# fullprop.net
KiCad netlist of a schematic drawn in EAGLE
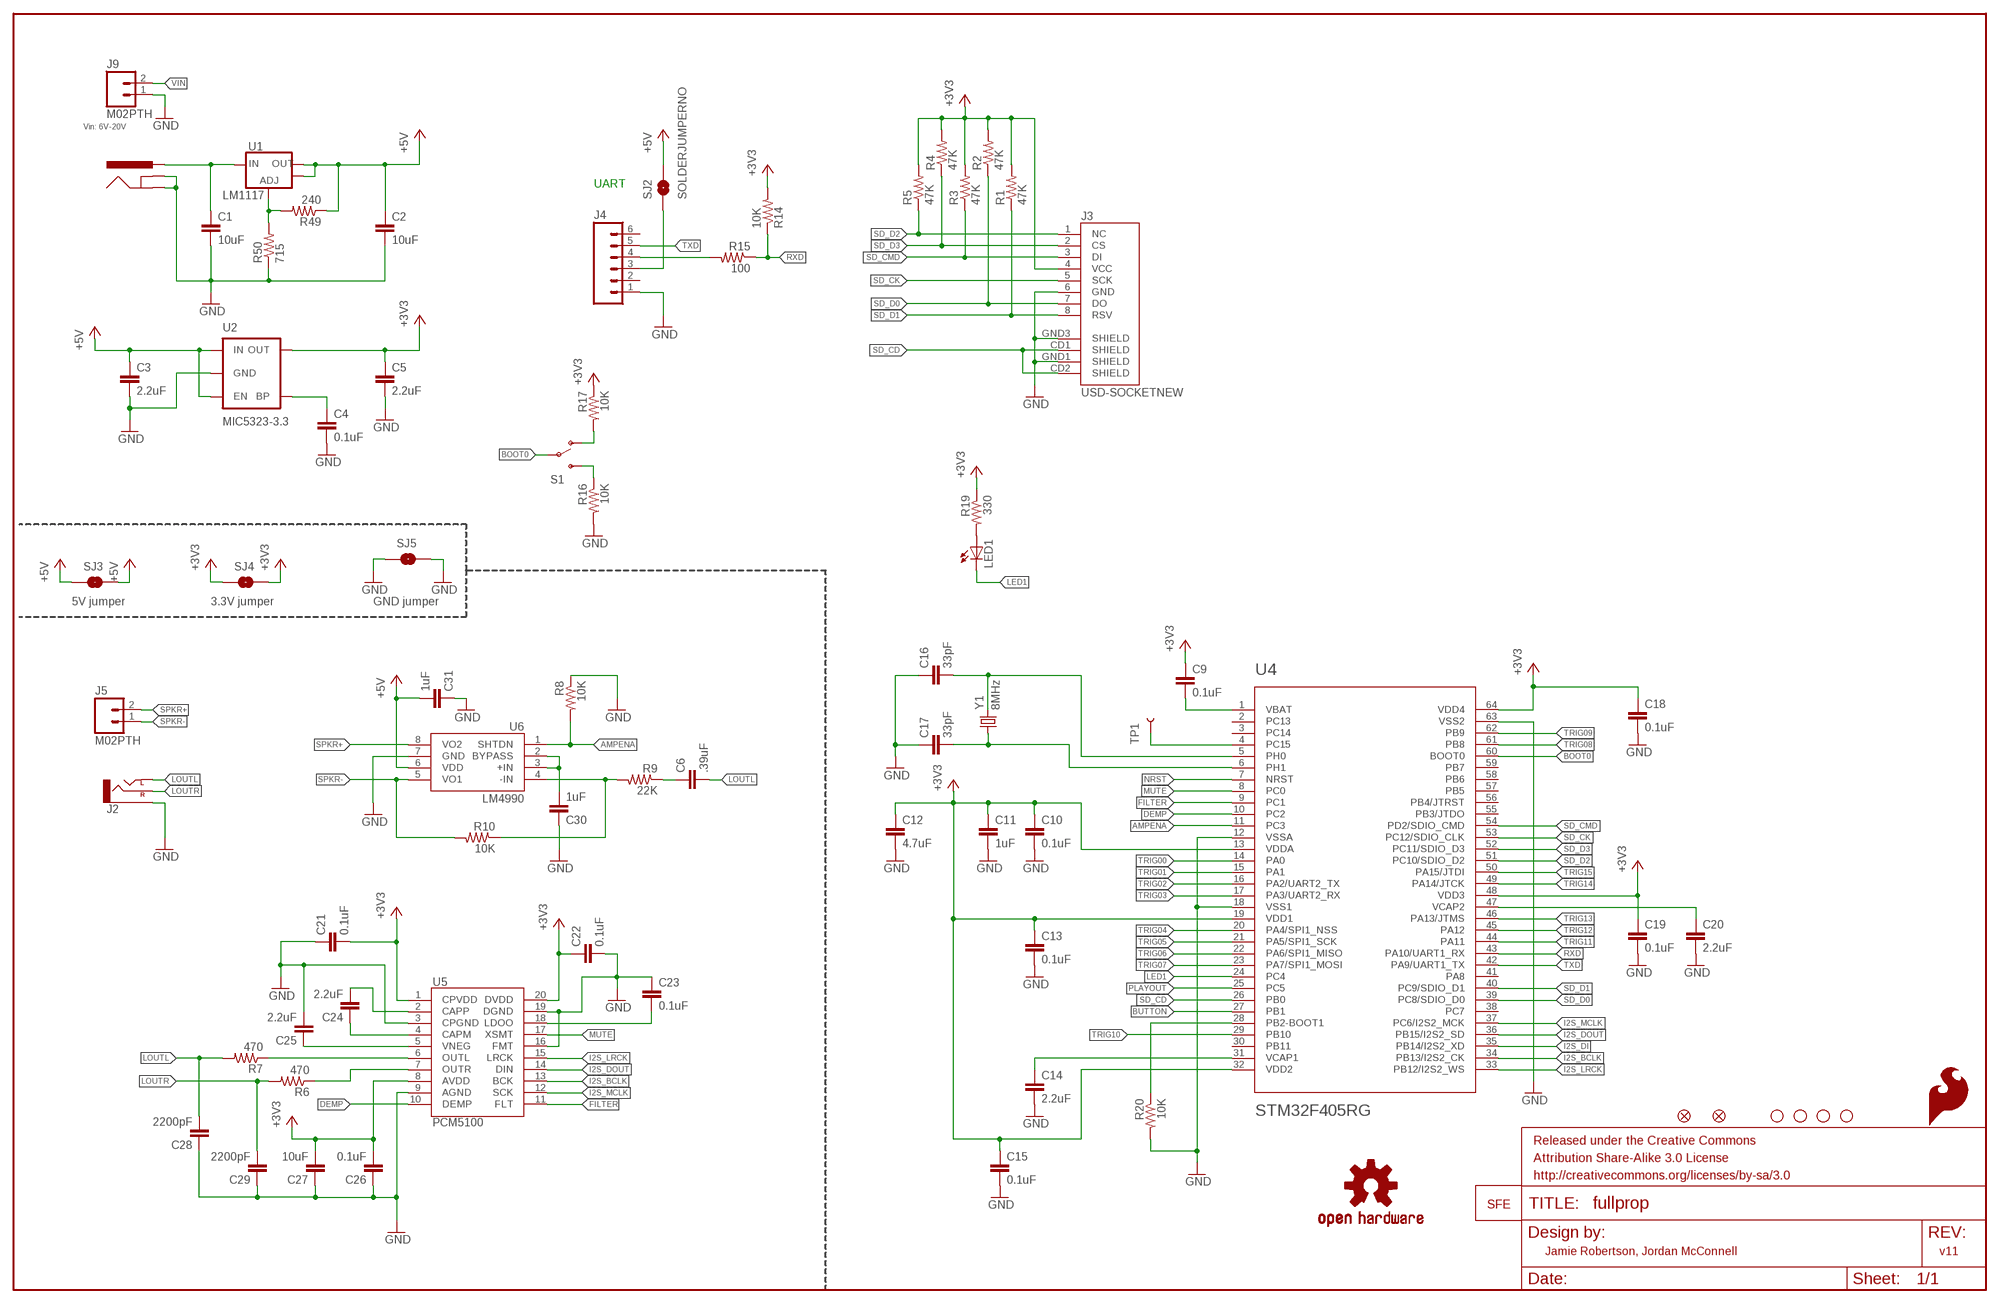
[diagram p0: schematic, sheet 1]

(export (version "E")
  (design (tool "Eeschema 10.0.6"))
  (components
    (comp (ref "C1")
      (value "10uF")
      (footprint "eagle-import:1210")
      (libsource (lib "eagle-import") (part "10UF50V20%(1210)"))
    )
    (comp (ref "C2")
      (value "10uF")
      (footprint "eagle-import:0805")
      (libsource (lib "eagle-import") (part "1UF-25V-10%(0805)"))
    )
    (comp (ref "C3")
      (value "2.2uF")
      (footprint "eagle-import:0805")
      (libsource (lib "eagle-import") (part "1UF-25V-10%(0805)"))
    )
    (comp (ref "C4")
      (value "0.1uF")
      (footprint "eagle-import:0603-CAP")
      (libsource (lib "eagle-import") (part "CAP0603-CAP"))
    )
    (comp (ref "C5")
      (value "2.2uF")
      (footprint "eagle-import:0805")
      (libsource (lib "eagle-import") (part "1UF-25V-10%(0805)"))
    )
    (comp (ref "C6")
      (value ".39uF")
      (footprint "eagle-import:0603-CAP")
      (libsource (lib "eagle-import") (part "CAP0603-CAP"))
    )
    (comp (ref "C9")
      (value "0.1uF")
      (footprint "eagle-import:0603-CAP")
      (libsource (lib "eagle-import") (part "CAP0603-CAP"))
    )
    (comp (ref "C10")
      (value "0.1uF")
      (footprint "eagle-import:0603-CAP")
      (libsource (lib "eagle-import") (part "CAP0603-CAP"))
    )
    (comp (ref "C11")
      (value "1uF")
      (footprint "eagle-import:0603-CAP")
      (libsource (lib "eagle-import") (part "CAP0603-CAP"))
    )
    (comp (ref "C12")
      (value "4.7uF")
      (footprint "eagle-import:0603-CAP")
      (libsource (lib "eagle-import") (part "CAP0603-CAP"))
    )
    (comp (ref "C13")
      (value "0.1uF")
      (footprint "eagle-import:0603-CAP")
      (libsource (lib "eagle-import") (part "CAP0603-CAP"))
    )
    (comp (ref "C14")
      (value "2.2uF")
      (footprint "eagle-import:0603-CAP")
      (libsource (lib "eagle-import") (part "CAP0603-CAP"))
    )
    (comp (ref "C15")
      (value "0.1uF")
      (footprint "eagle-import:0603-CAP")
      (libsource (lib "eagle-import") (part "CAP0603-CAP"))
    )
    (comp (ref "C16")
      (value "33pF")
      (footprint "eagle-import:0603-CAP")
      (libsource (lib "eagle-import") (part "CAP0603-CAP"))
    )
    (comp (ref "C17")
      (value "33pF")
      (footprint "eagle-import:0603-CAP")
      (libsource (lib "eagle-import") (part "CAP0603-CAP"))
    )
    (comp (ref "C18")
      (value "0.1uF")
      (footprint "eagle-import:0603-CAP")
      (libsource (lib "eagle-import") (part "CAP0603-CAP"))
    )
    (comp (ref "C19")
      (value "0.1uF")
      (footprint "eagle-import:0603-CAP")
      (libsource (lib "eagle-import") (part "CAP0603-CAP"))
    )
    (comp (ref "C20")
      (value "2.2uF")
      (footprint "eagle-import:0603-CAP")
      (libsource (lib "eagle-import") (part "CAP0603-CAP"))
    )
    (comp (ref "C21")
      (value "0.1uF")
      (footprint "eagle-import:0603-CAP")
      (libsource (lib "eagle-import") (part "CAP0603-CAP"))
    )
    (comp (ref "C22")
      (value "0.1uF")
      (footprint "eagle-import:0603-CAP")
      (libsource (lib "eagle-import") (part "CAP0603-CAP"))
    )
    (comp (ref "C23")
      (value "0.1uF")
      (footprint "eagle-import:0603-CAP")
      (libsource (lib "eagle-import") (part "CAP0603-CAP"))
    )
    (comp (ref "C24")
      (value "2.2uF")
      (footprint "eagle-import:0603-CAP")
      (libsource (lib "eagle-import") (part "CAP0603-CAP"))
    )
    (comp (ref "C25")
      (value "2.2uF")
      (footprint "eagle-import:0603-CAP")
      (libsource (lib "eagle-import") (part "CAP0603-CAP"))
    )
    (comp (ref "C26")
      (value "0.1uF")
      (footprint "eagle-import:0603-CAP")
      (libsource (lib "eagle-import") (part "CAP0603-CAP"))
    )
    (comp (ref "C27")
      (value "10uF")
      (footprint "eagle-import:0603-CAP")
      (libsource (lib "eagle-import") (part "CAP0603-CAP"))
    )
    (comp (ref "C28")
      (value "2200pF")
      (footprint "eagle-import:0603-CAP")
      (libsource (lib "eagle-import") (part "CAP0603-CAP"))
    )
    (comp (ref "C29")
      (value "2200pF")
      (footprint "eagle-import:0603-CAP")
      (libsource (lib "eagle-import") (part "CAP0603-CAP"))
    )
    (comp (ref "C30")
      (value "1uF")
      (footprint "eagle-import:0603-CAP")
      (libsource (lib "eagle-import") (part "CAP0603-CAP"))
    )
    (comp (ref "C31")
      (value "1uF")
      (footprint "eagle-import:0603-CAP")
      (libsource (lib "eagle-import") (part "CAP0603-CAP"))
    )
    (comp (ref "FID1")
      (value "FIDUCIAL1X2")
      (footprint "eagle-import:FIDUCIAL-1X2")
      (libsource (lib "eagle-import") (part "FIDUCIAL1X2"))
    )
    (comp (ref "FID2")
      (value "FIDUCIAL1X2")
      (footprint "eagle-import:FIDUCIAL-1X2")
      (libsource (lib "eagle-import") (part "FIDUCIAL1X2"))
    )
    (comp (ref "FRAME2")
      (value "FRAME-LEDGER")
      (footprint "eagle-import:CREATIVE_COMMONS")
      (libsource (lib "eagle-import") (part "FRAME-LEDGER"))
    )
    (comp (ref "J1")
      (value "5.5x2.1mm Barrel")
      (footprint "eagle-import:POWER_JACK_SMD_OVERPASTE_REDBOARD_0603")
      (libsource (lib "eagle-import") (part "POWER_JACKOVERPASTE_REDBOARD_0603"))
    )
    (comp (ref "J2")
      (value "AUDIO-JACKSMD2")
      (footprint "eagle-import:AUDIO-JACK-3.5MM-SMD")
      (libsource (lib "eagle-import") (part "AUDIO-JACKSMD2"))
    )
    (comp (ref "J3")
      (value "USD-SOCKETNEW")
      (footprint "eagle-import:MICRO-SD-SOCKET-PP")
      (libsource (lib "eagle-import") (part "USD-SOCKETNEW"))
    )
    (comp (ref "J4")
      (value "M06SIP")
      (footprint "eagle-import:1X06")
      (libsource (lib "eagle-import") (part "M06SIP"))
    )
    (comp (ref "J5")
      (value "M02PTH")
      (footprint "eagle-import:1X02")
      (libsource (lib "eagle-import") (part "M02PTH"))
    )
    (comp (ref "J9")
      (value "M02PTH")
      (footprint "eagle-import:1X02")
      (libsource (lib "eagle-import") (part "M02PTH"))
    )
    (comp (ref "LED1")
      (value "LED0603")
      (footprint "eagle-import:LED-0603")
      (libsource (lib "eagle-import") (part "LED0603"))
    )
    (comp (ref "LOGO1")
      (value "OSHW-LOGOL")
      (footprint "eagle-import:OSHW-LOGO-L")
      (libsource (lib "eagle-import") (part "OSHW-LOGOL"))
    )
    (comp (ref "LOGO2")
      (value "LOGO-SFENEW")
      (footprint "eagle-import:SFE-NEW-WEBLOGO")
      (libsource (lib "eagle-import") (part "LOGO-SFENEW"))
    )
    (comp (ref "LOGO4")
      (value "SFE_LOGO_FLAME.2_INCH")
      (footprint "eagle-import:SFE_LOGO_FLAME_.2")
      (libsource (lib "eagle-import") (part "SFE_LOGO_FLAME.2_INCH"))
    )
    (comp (ref "R1")
      (value "47K")
      (footprint "eagle-import:0603-RES")
      (libsource (lib "eagle-import") (part "RESISTOR0603-RES"))
    )
    (comp (ref "R2")
      (value "47K")
      (footprint "eagle-import:0603-RES")
      (libsource (lib "eagle-import") (part "RESISTOR0603-RES"))
    )
    (comp (ref "R3")
      (value "47K")
      (footprint "eagle-import:0603-RES")
      (libsource (lib "eagle-import") (part "RESISTOR0603-RES"))
    )
    (comp (ref "R4")
      (value "47K")
      (footprint "eagle-import:0603-RES")
      (libsource (lib "eagle-import") (part "RESISTOR0603-RES"))
    )
    (comp (ref "R5")
      (value "47K")
      (footprint "eagle-import:0603-RES")
      (libsource (lib "eagle-import") (part "RESISTOR0603-RES"))
    )
    (comp (ref "R6")
      (value "470")
      (footprint "eagle-import:0603-RES")
      (libsource (lib "eagle-import") (part "RESISTOR0603-RES"))
    )
    (comp (ref "R7")
      (value "470")
      (footprint "eagle-import:0603-RES")
      (libsource (lib "eagle-import") (part "RESISTOR0603-RES"))
    )
    (comp (ref "R8")
      (value "10K")
      (footprint "eagle-import:0603-RES")
      (libsource (lib "eagle-import") (part "RESISTOR0603-RES"))
    )
    (comp (ref "R9")
      (value "22K")
      (footprint "eagle-import:0603-RES")
      (libsource (lib "eagle-import") (part "RESISTOR0603-RES"))
    )
    (comp (ref "R10")
      (value "10K")
      (footprint "eagle-import:0603-RES")
      (libsource (lib "eagle-import") (part "RESISTOR0603-RES"))
    )
    (comp (ref "R14")
      (value "10K")
      (footprint "eagle-import:0603-RES")
      (libsource (lib "eagle-import") (part "RESISTOR0603-RES"))
    )
    (comp (ref "R15")
      (value "100")
      (footprint "eagle-import:0603-RES")
      (libsource (lib "eagle-import") (part "RESISTOR0603-RES"))
    )
    (comp (ref "R16")
      (value "10K")
      (footprint "eagle-import:0603-RES")
      (libsource (lib "eagle-import") (part "RESISTOR0603-RES"))
    )
    (comp (ref "R17")
      (value "10K")
      (footprint "eagle-import:0603-RES")
      (libsource (lib "eagle-import") (part "RESISTOR0603-RES"))
    )
    (comp (ref "R19")
      (value "330")
      (footprint "eagle-import:0603-RES")
      (libsource (lib "eagle-import") (part "RESISTOR0603-RES"))
    )
    (comp (ref "R20")
      (value "10K")
      (footprint "eagle-import:0603-RES")
      (libsource (lib "eagle-import") (part "RESISTOR0603-RES"))
    )
    (comp (ref "R49")
      (value "240")
      (footprint "eagle-import:0603-RES")
      (libsource (lib "eagle-import") (part "240OHM1/10W1%(0603)"))
    )
    (comp (ref "R50")
      (value "715")
      (footprint "eagle-import:0603-RES")
      (libsource (lib "eagle-import") (part "RESISTOR0603"))
    )
    (comp (ref "S1")
      (value "SWITCH-SPDT-SMD-A")
      (footprint "eagle-import:SWITCH-SPST-SMD-A")
      (libsource (lib "eagle-import") (part "SWITCH-SPDT-SMD-A"))
    )
    (comp (ref "SJ2")
      (value "SOLDERJUMPERNO")
      (footprint "eagle-import:SJ_2S-NO")
      (libsource (lib "eagle-import") (part "SOLDERJUMPERNO"))
    )
    (comp (ref "SJ3")
      (value "SOLDERJUMPERTRACE")
      (footprint "eagle-import:SJ_2S-TRACE")
      (libsource (lib "eagle-import") (part "SOLDERJUMPERTRACE"))
    )
    (comp (ref "SJ4")
      (value "SOLDERJUMPERTRACE")
      (footprint "eagle-import:SJ_2S-TRACE")
      (libsource (lib "eagle-import") (part "SOLDERJUMPERTRACE"))
    )
    (comp (ref "SJ5")
      (value "SOLDERJUMPERTRACE")
      (footprint "eagle-import:SJ_2S-TRACE")
      (libsource (lib "eagle-import") (part "SOLDERJUMPERTRACE"))
    )
    (comp (ref "STANDOFF1")
      (value "STAND-OFF")
      (footprint "eagle-import:STAND-OFF")
      (libsource (lib "eagle-import") (part "STAND-OFF"))
    )
    (comp (ref "STANDOFF2")
      (value "STAND-OFF")
      (footprint "eagle-import:STAND-OFF")
      (libsource (lib "eagle-import") (part "STAND-OFF"))
    )
    (comp (ref "STANDOFF3")
      (value "STAND-OFF")
      (footprint "eagle-import:STAND-OFF")
      (libsource (lib "eagle-import") (part "STAND-OFF"))
    )
    (comp (ref "STANDOFF4")
      (value "STAND-OFF")
      (footprint "eagle-import:STAND-OFF")
      (libsource (lib "eagle-import") (part "STAND-OFF"))
    )
    (comp (ref "TP1")
      (value "TEST-POINTTP_15TH_THRU")
      (footprint "eagle-import:TP_15TH")
      (libsource (lib "eagle-import") (part "TEST-POINTTP_15TH_THRU"))
    )
    (comp (ref "U1")
      (value "V_REG_LM1117SOT223")
      (footprint "eagle-import:SOT223")
      (libsource (lib "eagle-import") (part "V_REG_LM1117SOT223"))
    )
    (comp (ref "U2")
      (value "MIC5323-3.3")
      (footprint "eagle-import:SOT23-5")
      (libsource (lib "eagle-import") (part "MIC52053.3V"))
    )
    (comp (ref "U4")
      (value "STM32F405RG")
      (footprint "eagle-import:TQFP64")
      (libsource (lib "eagle-import") (part "STM32F405RG"))
    )
    (comp (ref "U5")
      (value "PCM5100")
      (footprint "eagle-import:PW_R-PDSO-G20")
      (libsource (lib "eagle-import") (part "PCM5100"))
    )
    (comp (ref "U6")
      (value "LM4990")
      (footprint "eagle-import:S-PDSO-G08")
      (libsource (lib "eagle-import") (part "LM4990"))
    )
    (comp (ref "Y1")
      (value "8MHz")
      (footprint "eagle-import:HC49UP")
      (libsource (lib "eagle-import") (part "CRYSTALSMD"))
    )
  )
  (nets
    (net (code "1") (name "+3V3") (class "Default")
      (node (ref "C10") (pin "1") (pinfunction "1_1") (pintype "passive"))
      (node (ref "C11") (pin "1") (pinfunction "1_1") (pintype "passive"))
      (node (ref "C12") (pin "1") (pinfunction "1_1") (pintype "passive"))
      (node (ref "C13") (pin "1") (pinfunction "1_1") (pintype "passive"))
      (node (ref "C15") (pin "1") (pinfunction "1_1") (pintype "passive"))
      (node (ref "C18") (pin "1") (pinfunction "1_1") (pintype "passive"))
      (node (ref "C19") (pin "1") (pinfunction "1_1") (pintype "passive"))
      (node (ref "C21") (pin "2") (pinfunction "2_2") (pintype "passive"))
      (node (ref "C22") (pin "1") (pinfunction "1_1") (pintype "passive"))
      (node (ref "C26") (pin "2") (pinfunction "2_2") (pintype "passive"))
      (node (ref "C27") (pin "2") (pinfunction "2_2") (pintype "passive"))
      (node (ref "C5") (pin "1") (pinfunction "1_1") (pintype "passive"))
      (node (ref "C9") (pin "1") (pinfunction "1_1") (pintype "passive"))
      (node (ref "J3") (pin "4") (pinfunction "VCC_4") (pintype "bidirectional"))
      (node (ref "R1") (pin "2") (pinfunction "2_2") (pintype "passive"))
      (node (ref "R14") (pin "2") (pinfunction "2_2") (pintype "passive"))
      (node (ref "R17") (pin "1") (pinfunction "1_1") (pintype "passive"))
      (node (ref "R19") (pin "1") (pinfunction "1_1") (pintype "passive"))
      (node (ref "R2") (pin "2") (pinfunction "2_2") (pintype "passive"))
      (node (ref "R3") (pin "2") (pinfunction "2_2") (pintype "passive"))
      (node (ref "R4") (pin "2") (pinfunction "2_2") (pintype "passive"))
      (node (ref "R5") (pin "2") (pinfunction "2_2") (pintype "passive"))
      (node (ref "SJ4") (pin "1") (pinfunction "1_1") (pintype "passive"))
      (node (ref "SJ4") (pin "2") (pinfunction "2_2") (pintype "passive"))
      (node (ref "U2") (pin "5") (pinfunction "OUT_5") (pintype "passive"))
      (node (ref "U4") (pin "13") (pinfunction "VDDA_13") (pintype "bidirectional"))
      (node (ref "U4") (pin "19") (pinfunction "VDD1_19") (pintype "bidirectional"))
      (node (ref "U4") (pin "32") (pinfunction "VDD2_32") (pintype "bidirectional"))
      (node (ref "U4") (pin "48") (pinfunction "VDD3_48") (pintype "bidirectional"))
      (node (ref "U4") (pin "64") (pinfunction "VDD4_64") (pintype "bidirectional"))
      (node (ref "U5") (pin "1") (pinfunction "CPVDD_1") (pintype "bidirectional"))
      (node (ref "U5") (pin "20") (pinfunction "DVDD_20") (pintype "bidirectional"))
      (node (ref "U5") (pin "8") (pinfunction "AVDD_8") (pintype "bidirectional"))
    )
    (net (code "2") (name "+5V") (class "Default")
      (node (ref "C2") (pin "1") (pinfunction "1_1") (pintype "passive"))
      (node (ref "C3") (pin "1") (pinfunction "1_1") (pintype "passive"))
      (node (ref "C31") (pin "2") (pinfunction "2_2") (pintype "passive"))
      (node (ref "R49") (pin "1") (pinfunction "1_1") (pintype "passive"))
      (node (ref "SJ2") (pin "2") (pinfunction "2_2") (pintype "passive"))
      (node (ref "SJ3") (pin "1") (pinfunction "1_1") (pintype "passive"))
      (node (ref "SJ3") (pin "2") (pinfunction "2_2") (pintype "passive"))
      (node (ref "U1") (pin "2") (pinfunction "OUT_2") (pintype "output"))
      (node (ref "U1") (pin "4") (pinfunction "OUT_4") (pintype "output"))
      (node (ref "U2") (pin "1") (pinfunction "IN_1") (pintype "input"))
      (node (ref "U2") (pin "3") (pinfunction "EN_3") (pintype "input"))
      (node (ref "U6") (pin "6") (pinfunction "VDD_6") (pintype "bidirectional"))
    )
    (net (code "3") (name "AMPENA") (class "Default")
      (node (ref "R8") (pin "2") (pinfunction "2_2") (pintype "passive"))
      (node (ref "U4") (pin "11") (pinfunction "PC3_11") (pintype "bidirectional"))
      (node (ref "U6") (pin "1") (pinfunction "SHTDN_1") (pintype "bidirectional"))
    )
    (net (code "4") (name "BOOT0") (class "Default")
      (node (ref "S1") (pin "2") (pinfunction "P_2") (pintype "passive"))
      (node (ref "U4") (pin "60") (pinfunction "BOOT0_60") (pintype "bidirectional"))
    )
    (net (code "5") (name "BUTTON") (class "Default")
      (node (ref "U4") (pin "27") (pinfunction "PB1_27") (pintype "bidirectional"))
    )
    (net (code "6") (name "DEMP") (class "Default")
      (node (ref "U4") (pin "10") (pinfunction "PC2_10") (pintype "bidirectional"))
      (node (ref "U5") (pin "10") (pinfunction "DEMP_10") (pintype "bidirectional"))
    )
    (net (code "7") (name "FILTER") (class "Default")
      (node (ref "U4") (pin "9") (pinfunction "PC1_9") (pintype "bidirectional"))
      (node (ref "U5") (pin "11") (pinfunction "FLT_11") (pintype "bidirectional"))
    )
    (net (code "8") (name "GND") (class "Default")
      (node (ref "C1") (pin "2") (pinfunction "2_2") (pintype "passive"))
      (node (ref "C10") (pin "2") (pinfunction "2_2") (pintype "passive"))
      (node (ref "C11") (pin "2") (pinfunction "2_2") (pintype "passive"))
      (node (ref "C12") (pin "2") (pinfunction "2_2") (pintype "passive"))
      (node (ref "C13") (pin "2") (pinfunction "2_2") (pintype "passive"))
      (node (ref "C14") (pin "2") (pinfunction "2_2") (pintype "passive"))
      (node (ref "C15") (pin "2") (pinfunction "2_2") (pintype "passive"))
      (node (ref "C16") (pin "1") (pinfunction "1_1") (pintype "passive"))
      (node (ref "C17") (pin "1") (pinfunction "1_1") (pintype "passive"))
      (node (ref "C18") (pin "2") (pinfunction "2_2") (pintype "passive"))
      (node (ref "C19") (pin "2") (pinfunction "2_2") (pintype "passive"))
      (node (ref "C2") (pin "2") (pinfunction "2_2") (pintype "passive"))
      (node (ref "C20") (pin "2") (pinfunction "2_2") (pintype "passive"))
      (node (ref "C21") (pin "1") (pinfunction "1_1") (pintype "passive"))
      (node (ref "C22") (pin "2") (pinfunction "2_2") (pintype "passive"))
      (node (ref "C23") (pin "1") (pinfunction "1_1") (pintype "passive"))
      (node (ref "C25") (pin "2") (pinfunction "2_2") (pintype "passive"))
      (node (ref "C26") (pin "1") (pinfunction "1_1") (pintype "passive"))
      (node (ref "C27") (pin "1") (pinfunction "1_1") (pintype "passive"))
      (node (ref "C28") (pin "1") (pinfunction "1_1") (pintype "passive"))
      (node (ref "C29") (pin "1") (pinfunction "1_1") (pintype "passive"))
      (node (ref "C3") (pin "2") (pinfunction "2_2") (pintype "passive"))
      (node (ref "C30") (pin "1") (pinfunction "1_1") (pintype "passive"))
      (node (ref "C31") (pin "1") (pinfunction "1_1") (pintype "passive"))
      (node (ref "C4") (pin "2") (pinfunction "2_2") (pintype "passive"))
      (node (ref "C5") (pin "2") (pinfunction "2_2") (pintype "passive"))
      (node (ref "J1") (pin "GND") (pinfunction "GNDBREAK_GND") (pintype "bidirectional"))
      (node (ref "J1") (pin "P$4") (pinfunction "GND_P$4") (pintype "bidirectional"))
      (node (ref "J2") (pin "SLEEVE") (pinfunction "SLEEVE_SLEEVE") (pintype "bidirectional"))
      (node (ref "J3") (pin "6") (pinfunction "GND_6") (pintype "bidirectional"))
      (node (ref "J3") (pin "GND1") (pinfunction "SHIELD_GND1") (pintype "bidirectional"))
      (node (ref "J3") (pin "GND3") (pinfunction "SHIELD_GND3") (pintype "bidirectional"))
      (node (ref "J4") (pin "1") (pinfunction "1_1") (pintype "passive"))
      (node (ref "J9") (pin "1") (pinfunction "1_1") (pintype "passive"))
      (node (ref "R16") (pin "2") (pinfunction "2_2") (pintype "passive"))
      (node (ref "R20") (pin "2") (pinfunction "2_2") (pintype "passive"))
      (node (ref "R50") (pin "1") (pinfunction "1_1") (pintype "passive"))
      (node (ref "R8") (pin "1") (pinfunction "1_1") (pintype "passive"))
      (node (ref "SJ5") (pin "1") (pinfunction "1_1") (pintype "passive"))
      (node (ref "SJ5") (pin "2") (pinfunction "2_2") (pintype "passive"))
      (node (ref "U2") (pin "2") (pinfunction "GND_2") (pintype "input"))
      (node (ref "U4") (pin "12") (pinfunction "VSSA_12") (pintype "bidirectional"))
      (node (ref "U4") (pin "18") (pinfunction "VSS1_18") (pintype "bidirectional"))
      (node (ref "U4") (pin "63") (pinfunction "VSS2_63") (pintype "bidirectional"))
      (node (ref "U5") (pin "16") (pinfunction "FMT_16") (pintype "bidirectional"))
      (node (ref "U5") (pin "19") (pinfunction "DGND_19") (pintype "bidirectional"))
      (node (ref "U5") (pin "3") (pinfunction "CPGND_3") (pintype "bidirectional"))
      (node (ref "U5") (pin "9") (pinfunction "AGND_9") (pintype "bidirectional"))
      (node (ref "U6") (pin "7") (pinfunction "GND_7") (pintype "bidirectional"))
    )
    (net (code "9") (name "I2S_BCLK") (class "Default")
      (node (ref "U4") (pin "34") (pinfunction "PB13/I2S2_CK_34") (pintype "bidirectional"))
      (node (ref "U5") (pin "13") (pinfunction "BCK_13") (pintype "bidirectional"))
    )
    (net (code "10") (name "I2S_DI") (class "Default")
      (node (ref "U4") (pin "35") (pinfunction "PB14/I2S2_XD_35") (pintype "bidirectional"))
    )
    (net (code "11") (name "I2S_DOUT") (class "Default")
      (node (ref "U4") (pin "36") (pinfunction "PB15/I2S2_SD_36") (pintype "bidirectional"))
      (node (ref "U5") (pin "14") (pinfunction "DIN_14") (pintype "bidirectional"))
    )
    (net (code "12") (name "I2S_LRCK") (class "Default")
      (node (ref "U4") (pin "33") (pinfunction "PB12/I2S2_WS_33") (pintype "bidirectional"))
      (node (ref "U5") (pin "15") (pinfunction "LRCK_15") (pintype "bidirectional"))
    )
    (net (code "13") (name "I2S_MCLK") (class "Default")
      (node (ref "U4") (pin "37") (pinfunction "PC6/I2S2_MCK_37") (pintype "bidirectional"))
      (node (ref "U5") (pin "12") (pinfunction "SCK_12") (pintype "bidirectional"))
    )
    (net (code "14") (name "LED1") (class "Default")
      (node (ref "LED1") (pin "C") (pinfunction "C_C") (pintype "passive"))
      (node (ref "U4") (pin "24") (pinfunction "PC4_24") (pintype "bidirectional"))
    )
    (net (code "15") (name "LOUTL") (class "Default")
      (node (ref "C28") (pin "2") (pinfunction "2_2") (pintype "passive"))
      (node (ref "C6") (pin "2") (pinfunction "2_2") (pintype "passive"))
      (node (ref "J2") (pin "TIP") (pinfunction "LEFT_TIP") (pintype "bidirectional"))
      (node (ref "R7") (pin "2") (pinfunction "2_2") (pintype "passive"))
    )
    (net (code "16") (name "LOUTR") (class "Default")
      (node (ref "C29") (pin "2") (pinfunction "2_2") (pintype "passive"))
      (node (ref "J2") (pin "RING") (pinfunction "RIGHT_RING") (pintype "bidirectional"))
      (node (ref "R6") (pin "2") (pinfunction "2_2") (pintype "passive"))
    )
    (net (code "17") (name "MUTE") (class "Default")
      (node (ref "U4") (pin "8") (pinfunction "PC0_8") (pintype "bidirectional"))
      (node (ref "U5") (pin "17") (pinfunction "XSMT_17") (pintype "bidirectional"))
    )
    (net (code "18") (name "NRST") (class "Default")
      (node (ref "U4") (pin "7") (pinfunction "NRST_7") (pintype "bidirectional"))
    )
    (net (code "19") (name "Net-(C6-Pad1)") (class "Default")
      (node (ref "C6") (pin "1") (pinfunction "1_1") (pintype "passive"))
      (node (ref "R9") (pin "1") (pinfunction "1_1") (pintype "passive"))
    )
    (net (code "20") (name "Net-(J4-Pad3)") (class "Default")
      (node (ref "J4") (pin "3") (pinfunction "3_3") (pintype "passive"))
      (node (ref "SJ2") (pin "1") (pinfunction "1_1") (pintype "passive"))
    )
    (net (code "21") (name "Net-(J4-Pad4)") (class "Default")
      (node (ref "J4") (pin "4") (pinfunction "4_4") (pintype "passive"))
      (node (ref "R15") (pin "2") (pinfunction "2_2") (pintype "passive"))
    )
    (net (code "22") (name "Net-(LED1-PadA)") (class "Default")
      (node (ref "LED1") (pin "A") (pinfunction "A_A") (pintype "passive"))
      (node (ref "R19") (pin "2") (pinfunction "2_2") (pintype "passive"))
    )
    (net (code "23") (name "Net-(S1-O)") (class "Default")
      (node (ref "R17") (pin "2") (pinfunction "2_2") (pintype "passive"))
      (node (ref "S1") (pin "1") (pinfunction "O_1") (pintype "passive"))
    )
    (net (code "24") (name "Net-(S1-S)") (class "Default")
      (node (ref "R16") (pin "1") (pinfunction "1_1") (pintype "passive"))
      (node (ref "S1") (pin "3") (pinfunction "S_3") (pintype "passive"))
    )
    (net (code "25") (name "Net-(TP1-1)") (class "Default")
      (node (ref "TP1") (pin "P$1") (pinfunction "1_P$1") (pintype "bidirectional"))
      (node (ref "U4") (pin "4") (pinfunction "PC15_4") (pintype "bidirectional"))
    )
    (net (code "26") (name "Net-(U1-ADJ)") (class "Default")
      (node (ref "R49") (pin "2") (pinfunction "2_2") (pintype "passive"))
      (node (ref "R50") (pin "2") (pinfunction "2_2") (pintype "passive"))
      (node (ref "U1") (pin "1") (pinfunction "ADJ_1") (pintype "input"))
    )
    (net (code "27") (name "Net-(U2-BP)") (class "Default")
      (node (ref "C4") (pin "1") (pinfunction "1_1") (pintype "passive"))
      (node (ref "U2") (pin "4") (pinfunction "BP_4") (pintype "input"))
    )
    (net (code "28") (name "Net-(U4-PB2-BOOT1)") (class "Default")
      (node (ref "R20") (pin "1") (pinfunction "1_1") (pintype "passive"))
      (node (ref "U4") (pin "28") (pinfunction "PB2-BOOT1_28") (pintype "bidirectional"))
    )
    (net (code "29") (name "Net-(U4-PH0)") (class "Default")
      (node (ref "C16") (pin "2") (pinfunction "2_2") (pintype "passive"))
      (node (ref "U4") (pin "5") (pinfunction "PH0_5") (pintype "bidirectional"))
      (node (ref "Y1") (pin "2") (pinfunction "2_2") (pintype "passive"))
    )
    (net (code "30") (name "Net-(U4-PH1)") (class "Default")
      (node (ref "C17") (pin "2") (pinfunction "2_2") (pintype "passive"))
      (node (ref "U4") (pin "6") (pinfunction "PH1_6") (pintype "bidirectional"))
      (node (ref "Y1") (pin "1") (pinfunction "1_1") (pintype "passive"))
    )
    (net (code "31") (name "Net-(U4-VBAT)") (class "Default")
      (node (ref "C9") (pin "2") (pinfunction "2_2") (pintype "passive"))
      (node (ref "U4") (pin "1") (pinfunction "VBAT_1") (pintype "bidirectional"))
    )
    (net (code "32") (name "Net-(U4-VCAP1)") (class "Default")
      (node (ref "C14") (pin "1") (pinfunction "1_1") (pintype "passive"))
      (node (ref "U4") (pin "31") (pinfunction "VCAP1_31") (pintype "bidirectional"))
    )
    (net (code "33") (name "Net-(U4-VCAP2)") (class "Default")
      (node (ref "C20") (pin "1") (pinfunction "1_1") (pintype "passive"))
      (node (ref "U4") (pin "47") (pinfunction "VCAP2_47") (pintype "bidirectional"))
    )
    (net (code "34") (name "Net-(U5-CAPM)") (class "Default")
      (node (ref "C24") (pin "1") (pinfunction "1_1") (pintype "passive"))
      (node (ref "U5") (pin "4") (pinfunction "CAPM_4") (pintype "bidirectional"))
    )
    (net (code "35") (name "Net-(U5-CAPP)") (class "Default")
      (node (ref "C24") (pin "2") (pinfunction "2_2") (pintype "passive"))
      (node (ref "U5") (pin "2") (pinfunction "CAPP_2") (pintype "bidirectional"))
    )
    (net (code "36") (name "Net-(U5-LDOO)") (class "Default")
      (node (ref "C23") (pin "2") (pinfunction "2_2") (pintype "passive"))
      (node (ref "U5") (pin "18") (pinfunction "LDOO_18") (pintype "bidirectional"))
    )
    (net (code "37") (name "Net-(U5-OUTL)") (class "Default")
      (node (ref "R7") (pin "1") (pinfunction "1_1") (pintype "passive"))
      (node (ref "U5") (pin "6") (pinfunction "OUTL_6") (pintype "bidirectional"))
    )
    (net (code "38") (name "Net-(U5-OUTR)") (class "Default")
      (node (ref "R6") (pin "1") (pinfunction "1_1") (pintype "passive"))
      (node (ref "U5") (pin "7") (pinfunction "OUTR_7") (pintype "bidirectional"))
    )
    (net (code "39") (name "Net-(U5-VNEG)") (class "Default")
      (node (ref "C25") (pin "1") (pinfunction "1_1") (pintype "passive"))
      (node (ref "U5") (pin "5") (pinfunction "VNEG_5") (pintype "bidirectional"))
    )
    (net (code "40") (name "Net-(U6-+IN)") (class "Default")
      (node (ref "C30") (pin "2") (pinfunction "2_2") (pintype "passive"))
      (node (ref "U6") (pin "2") (pinfunction "BYPASS_2") (pintype "bidirectional"))
      (node (ref "U6") (pin "3") (pinfunction "+IN_3") (pintype "bidirectional"))
    )
    (net (code "41") (name "Net-(U6--IN)") (class "Default")
      (node (ref "R10") (pin "1") (pinfunction "1_1") (pintype "passive"))
      (node (ref "R9") (pin "2") (pinfunction "2_2") (pintype "passive"))
      (node (ref "U6") (pin "4") (pinfunction "-IN_4") (pintype "bidirectional"))
    )
    (net (code "42") (name "PLAYOUT") (class "Default")
      (node (ref "U4") (pin "25") (pinfunction "PC5_25") (pintype "bidirectional"))
    )
    (net (code "43") (name "RXD") (class "Default")
      (node (ref "R14") (pin "1") (pinfunction "1_1") (pintype "passive"))
      (node (ref "R15") (pin "1") (pinfunction "1_1") (pintype "passive"))
      (node (ref "U4") (pin "43") (pinfunction "PA10/UART1_RX_43") (pintype "bidirectional"))
    )
    (net (code "44") (name "SD_CD") (class "Default")
      (node (ref "J3") (pin "CD1") (pinfunction "SHIELD_CD1") (pintype "bidirectional"))
      (node (ref "J3") (pin "CD2") (pinfunction "SHIELD_CD2") (pintype "bidirectional"))
      (node (ref "U4") (pin "26") (pinfunction "PB0_26") (pintype "bidirectional"))
    )
    (net (code "45") (name "SD_CK") (class "Default")
      (node (ref "J3") (pin "5") (pinfunction "SCK_5") (pintype "bidirectional"))
      (node (ref "U4") (pin "53") (pinfunction "PC12/SDIO_CLK_53") (pintype "bidirectional"))
    )
    (net (code "46") (name "SD_CMD") (class "Default")
      (node (ref "J3") (pin "3") (pinfunction "DI_3") (pintype "bidirectional"))
      (node (ref "R3") (pin "1") (pinfunction "1_1") (pintype "passive"))
      (node (ref "U4") (pin "54") (pinfunction "PD2/SDIO_CMD_54") (pintype "bidirectional"))
    )
    (net (code "47") (name "SD_D0") (class "Default")
      (node (ref "J3") (pin "7") (pinfunction "DO_7") (pintype "bidirectional"))
      (node (ref "R2") (pin "1") (pinfunction "1_1") (pintype "passive"))
      (node (ref "U4") (pin "39") (pinfunction "PC8/SDIO_D0_39") (pintype "bidirectional"))
    )
    (net (code "48") (name "SD_D1") (class "Default")
      (node (ref "J3") (pin "8") (pinfunction "RSV_8") (pintype "bidirectional"))
      (node (ref "R1") (pin "1") (pinfunction "1_1") (pintype "passive"))
      (node (ref "U4") (pin "40") (pinfunction "PC9/SDIO_D1_40") (pintype "bidirectional"))
    )
    (net (code "49") (name "SD_D2") (class "Default")
      (node (ref "J3") (pin "1") (pinfunction "NC_1") (pintype "bidirectional"))
      (node (ref "R5") (pin "1") (pinfunction "1_1") (pintype "passive"))
      (node (ref "U4") (pin "51") (pinfunction "PC10/SDIO_D2_51") (pintype "bidirectional"))
    )
    (net (code "50") (name "SD_D3") (class "Default")
      (node (ref "J3") (pin "2") (pinfunction "CS_2") (pintype "bidirectional"))
      (node (ref "R4") (pin "1") (pinfunction "1_1") (pintype "passive"))
      (node (ref "U4") (pin "52") (pinfunction "PC11/SDIO_D3_52") (pintype "bidirectional"))
    )
    (net (code "51") (name "SPKR+") (class "Default")
      (node (ref "J5") (pin "2") (pinfunction "2_2") (pintype "passive"))
      (node (ref "U6") (pin "8") (pinfunction "VO2_8") (pintype "bidirectional"))
    )
    (net (code "52") (name "SPKR-") (class "Default")
      (node (ref "J5") (pin "1") (pinfunction "1_1") (pintype "passive"))
      (node (ref "R10") (pin "2") (pinfunction "2_2") (pintype "passive"))
      (node (ref "U6") (pin "5") (pinfunction "VO1_5") (pintype "bidirectional"))
    )
    (net (code "53") (name "TRIG00") (class "Default")
      (node (ref "U4") (pin "14") (pinfunction "PA0_14") (pintype "bidirectional"))
    )
    (net (code "54") (name "TRIG01") (class "Default")
      (node (ref "U4") (pin "15") (pinfunction "PA1_15") (pintype "bidirectional"))
    )
    (net (code "55") (name "TRIG02") (class "Default")
      (node (ref "U4") (pin "16") (pinfunction "PA2/UART2_TX_16") (pintype "bidirectional"))
    )
    (net (code "56") (name "TRIG03") (class "Default")
      (node (ref "U4") (pin "17") (pinfunction "PA3/UART2_RX_17") (pintype "bidirectional"))
    )
    (net (code "57") (name "TRIG04") (class "Default")
      (node (ref "U4") (pin "20") (pinfunction "PA4/SPI1_NSS_20") (pintype "bidirectional"))
    )
    (net (code "58") (name "TRIG05") (class "Default")
      (node (ref "U4") (pin "21") (pinfunction "PA5/SPI1_SCK_21") (pintype "bidirectional"))
    )
    (net (code "59") (name "TRIG06") (class "Default")
      (node (ref "U4") (pin "22") (pinfunction "PA6/SPI1_MISO_22") (pintype "bidirectional"))
    )
    (net (code "60") (name "TRIG07") (class "Default")
      (node (ref "U4") (pin "23") (pinfunction "PA7/SPI1_MOSI_23") (pintype "bidirectional"))
    )
    (net (code "61") (name "TRIG08") (class "Default")
      (node (ref "U4") (pin "61") (pinfunction "PB8_61") (pintype "bidirectional"))
    )
    (net (code "62") (name "TRIG09") (class "Default")
      (node (ref "U4") (pin "62") (pinfunction "PB9_62") (pintype "bidirectional"))
    )
    (net (code "63") (name "TRIG10") (class "Default")
      (node (ref "U4") (pin "29") (pinfunction "PB10_29") (pintype "bidirectional"))
    )
    (net (code "64") (name "TRIG11") (class "Default")
      (node (ref "U4") (pin "44") (pinfunction "PA11_44") (pintype "bidirectional"))
    )
    (net (code "65") (name "TRIG12") (class "Default")
      (node (ref "U4") (pin "45") (pinfunction "PA12_45") (pintype "bidirectional"))
    )
    (net (code "66") (name "TRIG13") (class "Default")
      (node (ref "U4") (pin "46") (pinfunction "PA13/JTMS_46") (pintype "bidirectional"))
    )
    (net (code "67") (name "TRIG14") (class "Default")
      (node (ref "U4") (pin "49") (pinfunction "PA14/JTCK_49") (pintype "bidirectional"))
    )
    (net (code "68") (name "TRIG15") (class "Default")
      (node (ref "U4") (pin "50") (pinfunction "PA15/JTDI_50") (pintype "bidirectional"))
    )
    (net (code "69") (name "TXD") (class "Default")
      (node (ref "J4") (pin "5") (pinfunction "5_5") (pintype "passive"))
      (node (ref "U4") (pin "42") (pinfunction "PA9/UART1_TX_42") (pintype "bidirectional"))
    )
    (net (code "70") (name "VIN") (class "Default")
      (node (ref "C1") (pin "1") (pinfunction "1_1") (pintype "passive"))
      (node (ref "J1") (pin "VIN0") (pinfunction "PWR_VIN0") (pintype "bidirectional"))
      (node (ref "J9") (pin "2") (pinfunction "2_2") (pintype "passive"))
      (node (ref "U1") (pin "3") (pinfunction "IN_3") (pintype "input"))
    )
    (net (code "71") (name "unconnected-(J4-Pad2)") (class "Default")
      (node (ref "J4") (pin "2") (pinfunction "2_2") (pintype "passive"))
    )
    (net (code "72") (name "unconnected-(J4-Pad6)") (class "Default")
      (node (ref "J4") (pin "6") (pinfunction "6_6") (pintype "passive"))
    )
    (net (code "73") (name "unconnected-(U4-PA8-Pad41)") (class "Default")
      (node (ref "U4") (pin "41") (pinfunction "PA8_41") (pintype "bidirectional"))
    )
    (net (code "74") (name "unconnected-(U4-PB3{slash}JTDO-Pad55)") (class "Default")
      (node (ref "U4") (pin "55") (pinfunction "PB3/JTDO_55") (pintype "bidirectional"))
    )
    (net (code "75") (name "unconnected-(U4-PB4{slash}JTRST-Pad56)") (class "Default")
      (node (ref "U4") (pin "56") (pinfunction "PB4/JTRST_56") (pintype "bidirectional"))
    )
    (net (code "76") (name "unconnected-(U4-PB5-Pad57)") (class "Default")
      (node (ref "U4") (pin "57") (pinfunction "PB5_57") (pintype "bidirectional"))
    )
    (net (code "77") (name "unconnected-(U4-PB6-Pad58)") (class "Default")
      (node (ref "U4") (pin "58") (pinfunction "PB6_58") (pintype "bidirectional"))
    )
    (net (code "78") (name "unconnected-(U4-PB7-Pad59)") (class "Default")
      (node (ref "U4") (pin "59") (pinfunction "PB7_59") (pintype "bidirectional"))
    )
    (net (code "79") (name "unconnected-(U4-PB11-Pad30)") (class "Default")
      (node (ref "U4") (pin "30") (pinfunction "PB11_30") (pintype "bidirectional"))
    )
    (net (code "80") (name "unconnected-(U4-PC7-Pad38)") (class "Default")
      (node (ref "U4") (pin "38") (pinfunction "PC7_38") (pintype "bidirectional"))
    )
    (net (code "81") (name "unconnected-(U4-PC13-Pad2)") (class "Default")
      (node (ref "U4") (pin "2") (pinfunction "PC13_2") (pintype "bidirectional"))
    )
    (net (code "82") (name "unconnected-(U4-PC14-Pad3)") (class "Default")
      (node (ref "U4") (pin "3") (pinfunction "PC14_3") (pintype "bidirectional"))
    )
  )
)
